# EasyPIC16F1455.net
KiCad netlist of a schematic drawn in Altium Designer
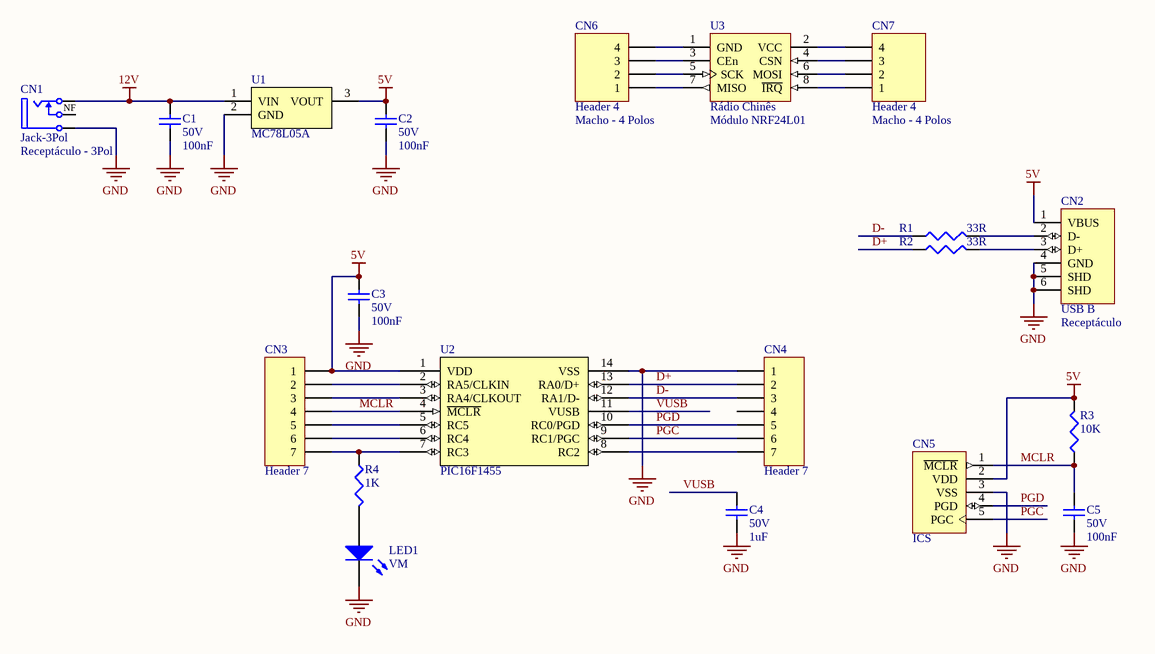
[diagram p0: EasyPIC16F1455.SchDoc]

(export (version "E")
  (design (tool "Eeschema 10.0.6"))
  (components
    (comp (ref "C1")
      (value "100nF")
      (footprint "CC0603")
      (description "Capacitor (Semiconductor SIM Model)")
      (fields (field (name "TENSÃO") "50V") (field (name "Comment") "Capacitor Cerâmico"))
      (libsource (lib "NavarroCAP") (part "Cap 100nF 50V 0603 X7R"))
    )
    (comp (ref "C2")
      (value "100nF")
      (footprint "CC0603")
      (description "Capacitor (Semiconductor SIM Model)")
      (fields (field (name "TENSÃO") "50V") (field (name "Comment") "Capacitor Cerâmico"))
      (libsource (lib "NavarroCAP") (part "Cap 100nF 50V 0603 X7R"))
    )
    (comp (ref "C3")
      (value "100nF")
      (footprint "CC0603")
      (description "Capacitor (Semiconductor SIM Model)")
      (fields (field (name "TENSÃO") "50V") (field (name "Comment") "Capacitor Cerâmico"))
      (libsource (lib "NavarroCAP") (part "Cap 100nF 50V 0603 X7R"))
    )
    (comp (ref "C4")
      (value "1uF")
      (footprint "CC0603")
      (description "Capacitor (Semiconductor SIM Model)")
      (fields (field (name "TENSÃO") "50V") (field (name "Comment") "Capacitor Cerâmico"))
      (libsource (lib "NavarroCAP") (part "Cap 1uF 50V 0603 X5R"))
    )
    (comp (ref "C5")
      (value "100nF")
      (footprint "CC0603")
      (description "Capacitor (Semiconductor SIM Model)")
      (fields (field (name "TENSÃO") "50V") (field (name "Comment") "Capacitor Cerâmico"))
      (libsource (lib "NavarroCAP") (part "Cap 100nF 50V 0603 X7R"))
    )
    (comp (ref "CN1")
      (value "Jack-3Pol")
      (footprint "CONN_JACK-FONTE_3N")
      (description "Jack Socket, Thru-Hole, Vertical, 2 Conductors, 3 Contacts Single Switch, Normally Closed")
      (fields (field (name "ALTIUM_VALUE") "Receptáculo - 3Pol"))
      (libsource (lib "NavarroCON") (part "Jack-3Pol"))
    )
    (comp (ref "CN2")
      (value "USB B")
      (footprint "CONN_USB-B_RCPT-H")
      (description "Conector Jack USB B, Through Hole, Right Angle, Horizontal")
      (fields (field (name "ALTIUM_VALUE") "Receptáculo"))
      (libsource (lib "NavarroCON") (part "USB B RCPT-H"))
    )
    (comp (ref "CN3")
      (value "Header 7")
      (footprint "CONN HDR1X7")
      (description "Header, 7-Pin")
      (libsource (lib "") (part "Header 7_1"))
    )
    (comp (ref "CN4")
      (value "Header 7")
      (footprint "CONN HDR1X7")
      (description "Header, 7-Pin")
      (libsource (lib "NavarroCON") (part "Header 7"))
    )
    (comp (ref "CN5")
      (value "ICS")
      (footprint "CONN HDR1X5")
      (description "Header, 5-Pin")
      (libsource (lib "NavarroCON") (part "Header 5 ICS"))
    )
    (comp (ref "CN6")
      (value "Header 4")
      (footprint "CONN HDR1X4")
      (description "Header, 4-Pin")
      (fields (field (name "ALTIUM_VALUE") "Macho - 4 Polos"))
      (libsource (lib "") (part "Header 4_1"))
    )
    (comp (ref "CN7")
      (value "Header 4")
      (footprint "CONN HDR1X4")
      (description "Header, 4-Pin")
      (fields (field (name "ALTIUM_VALUE") "Macho - 4 Polos"))
      (libsource (lib "NavarroCON") (part "Header 4"))
    )
    (comp (ref "LED1")
      (value "VM")
      (footprint "LED 0603")
      (description "LED")
      (libsource (lib "NavarroSEMI") (part "LED"))
    )
    (comp (ref "R1")
      (value "33R")
      (footprint "CC0603")
      (description "Resistor")
      (libsource (lib "NavarroRES") (part "Res 33R 1% 0603 1/10W"))
    )
    (comp (ref "R2")
      (value "33R")
      (footprint "CC0603")
      (description "Resistor")
      (libsource (lib "NavarroRES") (part "Res 33R 1% 0603 1/10W"))
    )
    (comp (ref "R3")
      (value "10K")
      (footprint "CC0603")
      (description "Resistor")
      (libsource (lib "NavarroRES") (part "Res 10K 1% 0603 1/10W"))
    )
    (comp (ref "R4")
      (value "1K")
      (footprint "CC0603")
      (description "Resistor")
      (libsource (lib "NavarroRES") (part "Res 1K 1% 0603 1/10W"))
    )
    (comp (ref "U1")
      (value "MC78L05A")
      (footprint "SOT-89-3N")
      (description "Regulador Linear 5V")
      (libsource (lib "Navarro") (part "MC78L05"))
    )
    (comp (ref "U2")
      (value "PIC16F1455")
      (footprint "SOIC-14N")
      (description "Microcontrolador PIC")
      (libsource (lib "Navarro") (part "PIC16F1455"))
    )
    (comp (ref "U3")
      (value "Rádio Chinês")
      (footprint "MOD_NRF24L01")
      (description "Módulo de rádio com nRF24L01")
      (fields
        (field (name "ALTIUM_VALUE") "Módulo NRF24L01")
        (field (name "COMPONENTLINK1URL") "D:\\Tecnoclade\\Datasheet\\Modulo RF Chinês NRF24L01.pdf")
      )
      (libsource (lib "Navarro") (part "Modulo RF NRF24L01"))
    )
  )
  (nets
    (net (code "1") (name "/D+") (class "Default")
      (node (ref "CN4") (pin "2") (pinfunction "2_2") (pintype "passive"))
      (node (ref "R2") (pin "1") (pinfunction "1_1") (pintype "passive"))
      (node (ref "U2") (pin "13") (pinfunction "RA0/D+_13") (pintype "bidirectional"))
    )
    (net (code "2") (name "/D-") (class "Default")
      (node (ref "CN4") (pin "3") (pinfunction "3_3") (pintype "passive"))
      (node (ref "R1") (pin "1") (pinfunction "1_1") (pintype "passive"))
      (node (ref "U2") (pin "12") (pinfunction "RA1/D-_12") (pintype "bidirectional"))
    )
    (net (code "3") (name "/MCLR") (class "Default")
      (node (ref "C5") (pin "2") (pinfunction "2_2") (pintype "passive"))
      (node (ref "CN3") (pin "4") (pinfunction "4_4") (pintype "passive"))
      (node (ref "CN5") (pin "1") (pinfunction "~{MCLR}_1") (pintype "output"))
      (node (ref "R3") (pin "1") (pinfunction "1_1") (pintype "passive"))
      (node (ref "U2") (pin "4") (pinfunction "~{MCLR}_4") (pintype "input"))
    )
    (net (code "4") (name "/PGC") (class "Default")
      (node (ref "CN4") (pin "6") (pinfunction "6_6") (pintype "passive"))
      (node (ref "CN5") (pin "5") (pinfunction "PGC_5") (pintype "passive"))
      (node (ref "U2") (pin "9") (pinfunction "RC1/PGC_9") (pintype "bidirectional"))
    )
    (net (code "5") (name "/PGD") (class "Default")
      (node (ref "CN4") (pin "5") (pinfunction "5_5") (pintype "passive"))
      (node (ref "CN5") (pin "4") (pinfunction "PGD_4") (pintype "bidirectional"))
      (node (ref "U2") (pin "10") (pinfunction "RC0/PGD_10") (pintype "bidirectional"))
    )
    (net (code "6") (name "/VUSB") (class "Default")
      (node (ref "C4") (pin "2") (pinfunction "2_2") (pintype "passive"))
      (node (ref "U2") (pin "11") (pinfunction "VUSB_11") (pintype "power_in"))
    )
    (net (code "7") (name "5V") (class "Default")
      (node (ref "C2") (pin "2") (pinfunction "2_2") (pintype "passive"))
      (node (ref "C3") (pin "2") (pinfunction "2_2") (pintype "passive"))
      (node (ref "CN2") (pin "1") (pinfunction "VBUS_1") (pintype "power_in"))
      (node (ref "CN3") (pin "1") (pinfunction "1_1") (pintype "passive"))
      (node (ref "CN5") (pin "2") (pinfunction "VDD_2") (pintype "power_in"))
      (node (ref "R3") (pin "2") (pinfunction "2_2") (pintype "passive"))
      (node (ref "U1") (pin "3") (pinfunction "VOUT_3") (pintype "power_in"))
      (node (ref "U2") (pin "1") (pinfunction "VDD_1") (pintype "power_in"))
    )
    (net (code "8") (name "12V") (class "Default")
      (node (ref "C1") (pin "2") (pinfunction "2_2") (pintype "passive"))
      (node (ref "CN1") (pin "1") (pinfunction "Centro_1") (pintype "power_in"))
      (node (ref "U1") (pin "1") (pinfunction "VIN_1") (pintype "power_in"))
    )
    (net (code "9") (name "GND") (class "Default")
      (node (ref "C1") (pin "1") (pinfunction "1_1") (pintype "passive"))
      (node (ref "C2") (pin "1") (pinfunction "1_1") (pintype "passive"))
      (node (ref "C3") (pin "1") (pinfunction "1_1") (pintype "passive"))
      (node (ref "C4") (pin "1") (pinfunction "1_1") (pintype "passive"))
      (node (ref "C5") (pin "1") (pinfunction "1_1") (pintype "passive"))
      (node (ref "CN1") (pin "2") (pinfunction "Malha_2") (pintype "power_in"))
      (node (ref "CN2") (pin "4") (pinfunction "GND_4") (pintype "power_in"))
      (node (ref "CN2") (pin "5") (pinfunction "SHD_5") (pintype "passive"))
      (node (ref "CN2") (pin "6") (pinfunction "SHD_6") (pintype "passive"))
      (node (ref "CN4") (pin "1") (pinfunction "1_1") (pintype "passive"))
      (node (ref "CN5") (pin "3") (pinfunction "VSS_3") (pintype "power_in"))
      (node (ref "LED1") (pin "2") (pinfunction "K_2") (pintype "passive"))
      (node (ref "U1") (pin "2") (pinfunction "GND_2") (pintype "power_in"))
      (node (ref "U2") (pin "14") (pinfunction "VSS_14") (pintype "power_in"))
    )
    (net (code "10") (name "Net-(CN2-D+)") (class "Default")
      (node (ref "CN2") (pin "3") (pinfunction "D+_3") (pintype "bidirectional"))
      (node (ref "R2") (pin "2") (pinfunction "2_2") (pintype "passive"))
    )
    (net (code "11") (name "Net-(CN2-D-)") (class "Default")
      (node (ref "CN2") (pin "2") (pinfunction "D-_2") (pintype "bidirectional"))
      (node (ref "R1") (pin "2") (pinfunction "2_2") (pintype "passive"))
    )
    (net (code "12") (name "Net-(LED1-A)") (class "Default")
      (node (ref "LED1") (pin "1") (pinfunction "A_1") (pintype "passive"))
      (node (ref "R4") (pin "2") (pinfunction "2_2") (pintype "passive"))
    )
    (net (code "13") (name "Net-(U2-RA4{slash}CLKOUT)") (class "Default")
      (node (ref "CN3") (pin "3") (pinfunction "3_3") (pintype "passive"))
      (node (ref "U2") (pin "3") (pinfunction "RA4/CLKOUT_3") (pintype "bidirectional"))
    )
    (net (code "14") (name "Net-(U2-RA5{slash}CLKIN)") (class "Default")
      (node (ref "CN3") (pin "2") (pinfunction "2_2") (pintype "passive"))
      (node (ref "U2") (pin "2") (pinfunction "RA5/CLKIN_2") (pintype "bidirectional"))
    )
    (net (code "15") (name "Net-(U2-RC2)") (class "Default")
      (node (ref "CN4") (pin "7") (pinfunction "7_7") (pintype "passive"))
      (node (ref "U2") (pin "8") (pinfunction "RC2_8") (pintype "bidirectional"))
    )
    (net (code "16") (name "Net-(U2-RC3)") (class "Default")
      (node (ref "CN3") (pin "7") (pinfunction "7_7") (pintype "passive"))
      (node (ref "R4") (pin "1") (pinfunction "1_1") (pintype "passive"))
      (node (ref "U2") (pin "7") (pinfunction "RC3_7") (pintype "bidirectional"))
    )
    (net (code "17") (name "Net-(U2-RC4)") (class "Default")
      (node (ref "CN3") (pin "6") (pinfunction "6_6") (pintype "passive"))
      (node (ref "U2") (pin "6") (pinfunction "RC4_6") (pintype "bidirectional"))
    )
    (net (code "18") (name "Net-(U2-RC5)") (class "Default")
      (node (ref "CN3") (pin "5") (pinfunction "5_5") (pintype "passive"))
      (node (ref "U2") (pin "5") (pinfunction "RC5_5") (pintype "bidirectional"))
    )
    (net (code "19") (name "Net-(U3-CEn)") (class "Default")
      (node (ref "CN6") (pin "3") (pinfunction "3_3") (pintype "passive"))
      (node (ref "U3") (pin "3") (pinfunction "CEn_3") (pintype "passive"))
    )
    (net (code "20") (name "Net-(U3-CSN)") (class "Default")
      (node (ref "CN7") (pin "3") (pinfunction "3_3") (pintype "passive"))
      (node (ref "U3") (pin "4") (pinfunction "CSN_4") (pintype "input"))
    )
    (net (code "21") (name "Net-(U3-GND)") (class "Default")
      (node (ref "CN6") (pin "4") (pinfunction "4_4") (pintype "passive"))
      (node (ref "U3") (pin "1") (pinfunction "GND_1") (pintype "power_in"))
    )
    (net (code "22") (name "Net-(U3-MISO)") (class "Default")
      (node (ref "CN6") (pin "1") (pinfunction "1_1") (pintype "passive"))
      (node (ref "U3") (pin "7") (pinfunction "MISO_7") (pintype "output"))
    )
    (net (code "23") (name "Net-(U3-MOSI)") (class "Default")
      (node (ref "CN7") (pin "2") (pinfunction "2_2") (pintype "passive"))
      (node (ref "U3") (pin "6") (pinfunction "MOSI_6") (pintype "input"))
    )
    (net (code "24") (name "Net-(U3-SCK)") (class "Default")
      (node (ref "CN6") (pin "2") (pinfunction "2_2") (pintype "passive"))
      (node (ref "U3") (pin "5") (pinfunction "SCK_5") (pintype "input"))
    )
    (net (code "25") (name "Net-(U3-VCC)") (class "Default")
      (node (ref "CN7") (pin "4") (pinfunction "4_4") (pintype "passive"))
      (node (ref "U3") (pin "2") (pinfunction "VCC_2") (pintype "power_in"))
    )
    (net (code "26") (name "Net-(U3-~{IRQ})") (class "Default")
      (node (ref "CN7") (pin "1") (pinfunction "1_1") (pintype "passive"))
      (node (ref "U3") (pin "8") (pinfunction "~{IRQ}_8") (pintype "input"))
    )
    (net (code "27") (name "unconnected-(CN1-NF-Pad3)") (class "Default")
      (node (ref "CN1") (pin "3") (pinfunction "NF_3") (pintype "passive"))
    )
    (net (code "28") (name "unconnected-(CN4-Pad4)") (class "Default")
      (node (ref "CN4") (pin "4") (pinfunction "4_4") (pintype "passive"))
    )
  )
)
